# Laser_STM32_System.net
KiCad netlist of a schematic drawn in Altium Designer
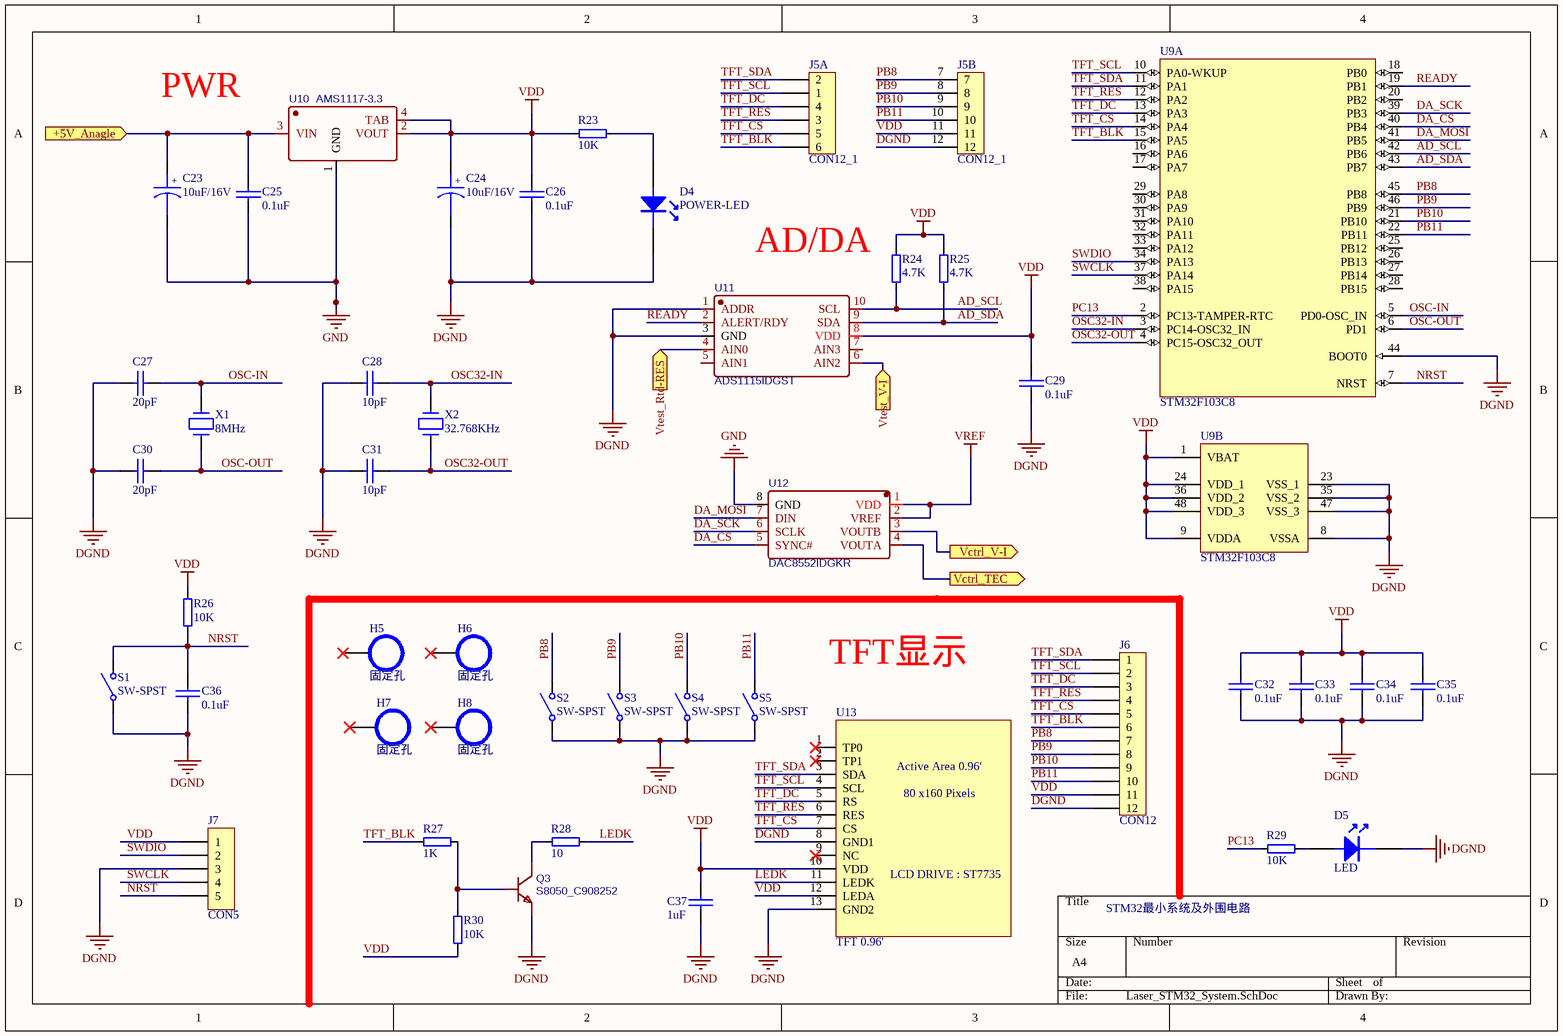
[diagram p0: Laser_STM32_System.SchDoc]

(export (version "E")
  (design (tool "Eeschema 10.0.6"))
  (components
    (comp (ref "C23")
      (value "10uF/16V")
      (footprint "CAP-TH_BD5.0-P2.00-D0.8-FD")
      (description "Capacitor")
      (libsource (lib "Laser Controller") (part "电解电容1"))
    )
    (comp (ref "C24")
      (value "10uF/16V")
      (footprint "CAP-TH_BD5.0-P2.00-D0.8-FD")
      (description "Capacitor")
      (libsource (lib "Laser Controller") (part "电解电容1"))
    )
    (comp (ref "C25")
      (value "0.1uF")
      (footprint "C 0603_M")
      (description "Capacitor")
      (libsource (lib "Laser Controller") (part "普通电容"))
    )
    (comp (ref "C26")
      (value "0.1uF")
      (footprint "C 0603_M")
      (description "Capacitor")
      (libsource (lib "Laser Controller") (part "普通电容"))
    )
    (comp (ref "C27")
      (value "20pF")
      (footprint "C 0603_M")
      (description "Capacitor")
      (libsource (lib "Laser Controller") (part "普通电容"))
    )
    (comp (ref "C28")
      (value "10pF")
      (footprint "C 0603_M")
      (description "Capacitor")
      (libsource (lib "Laser Controller") (part "普通电容"))
    )
    (comp (ref "C29")
      (value "0.1uF")
      (footprint "C 0603_M")
      (description "Capacitor")
      (libsource (lib "Laser Controller") (part "普通电容"))
    )
    (comp (ref "C30")
      (value "20pF")
      (footprint "C 0603_M")
      (description "Capacitor")
      (libsource (lib "Laser Controller") (part "普通电容"))
    )
    (comp (ref "C31")
      (value "10pF")
      (footprint "C 0603_M")
      (description "Capacitor")
      (libsource (lib "Laser Controller") (part "普通电容"))
    )
    (comp (ref "C32")
      (value "0.1uF")
      (footprint "C 0603_M")
      (description "Capacitor")
      (libsource (lib "Laser Controller") (part "普通电容"))
    )
    (comp (ref "C33")
      (value "0.1uF")
      (footprint "C 0603_M")
      (description "Capacitor")
      (libsource (lib "Laser Controller") (part "普通电容"))
    )
    (comp (ref "C34")
      (value "0.1uF")
      (footprint "C 0603_M")
      (description "Capacitor")
      (libsource (lib "Laser Controller") (part "普通电容"))
    )
    (comp (ref "C35")
      (value "0.1uF")
      (footprint "C 0603_M")
      (description "Capacitor")
      (libsource (lib "Laser Controller") (part "普通电容"))
    )
    (comp (ref "C36")
      (value "0.1uF")
      (footprint "C 0603_M")
      (description "Capacitor")
      (libsource (lib "Laser Controller") (part "普通电容"))
    )
    (comp (ref "C37")
      (value "1uF")
      (footprint "C 0603_M")
      (description "Capacitor")
      (libsource (lib "Laser Controller") (part "普通电容"))
    )
    (comp (ref "D4")
      (value "POWER-LED")
      (footprint "LED 0805R")
      (libsource (lib "Laser Controller") (part "发光二极管"))
    )
    (comp (ref "D5")
      (value "LED")
      (footprint "LED 0805R")
      (libsource (lib "Laser Controller") (part "发光二极管"))
    )
    (comp (ref "H5") (value "固定孔") (footprint "铜柱孔3") (libsource (lib "Laser Controller") (part "固定孔")))
    (comp (ref "H6") (value "固定孔") (footprint "铜柱孔3") (libsource (lib "Laser Controller") (part "固定孔")))
    (comp (ref "H7") (value "固定孔") (footprint "铜柱孔3") (libsource (lib "Laser Controller") (part "固定孔")))
    (comp (ref "H8") (value "固定孔") (footprint "铜柱孔3") (libsource (lib "Laser Controller") (part "固定孔")))
    (comp (ref "J5")
      (value "CON12_1")
      (footprint "XH2.54-WI-12P")
      (description "Connector")
      (libsource (lib "") (part "CON12_1_1"))
    )
    (comp (ref "J6")
      (value "CON12")
      (footprint "XH2.54-WI-12P")
      (description "Connector")
      (libsource (lib "Laser Controller") (part "CON12"))
    )
    (comp (ref "J7")
      (value "CON5")
      (footprint "排针-排母:HDR2.54-LI-5P")
      (description "Connector")
      (libsource (lib "Laser Controller") (part "CON5"))
    )
    (comp (ref "Q3")
      (value "S8050_C908252")
      (footprint "SOT-23-3_L2.9-W1.3-P1.90-LS2.4-BR")
      (fields
        (field (name "BOM_SUPPLIER PART") "C908252")
        (field (name "BOM_MANUFACTURER PART") "S8050")
        (field (name "CONTRIBUTOR") "LCSC")
      )
      (libsource (lib "Laser Controller") (part "S8050_C908252"))
    )
    (comp (ref "R23") (value "10K") (footprint "0603R") (libsource (lib "Laser Controller") (part "普通电阻")))
    (comp (ref "R24") (value "4.7K") (footprint "0603R") (libsource (lib "Laser Controller") (part "普通电阻")))
    (comp (ref "R25") (value "4.7K") (footprint "0603R") (libsource (lib "Laser Controller") (part "普通电阻")))
    (comp (ref "R26") (value "10K") (footprint "0603R") (libsource (lib "Laser Controller") (part "普通电阻")))
    (comp (ref "R27") (value "1K") (footprint "0603R") (libsource (lib "Laser Controller") (part "普通电阻")))
    (comp (ref "R28") (value "10") (footprint "0603R") (libsource (lib "Laser Controller") (part "普通电阻")))
    (comp (ref "R29") (value "10K") (footprint "0603R") (libsource (lib "Laser Controller") (part "普通电阻")))
    (comp (ref "R30") (value "10K") (footprint "0603R") (libsource (lib "Laser Controller") (part "普通电阻")))
    (comp (ref "S1")
      (value "SW-SPST")
      (footprint "TSW SMD-3*6*2.5")
      (description "Single-Pole, Single-Throw Switch")
      (fields (field (name "PUBLISHER") "Altium Limited"))
      (libsource (lib "Laser Controller") (part "SW-SPST"))
    )
    (comp (ref "S2")
      (value "SW-SPST")
      (footprint "TSW DIP-6*6*5")
      (description "Single-Pole, Single-Throw Switch")
      (fields (field (name "PUBLISHER") "Altium Limited"))
      (libsource (lib "Laser Controller") (part "SW-SPST"))
    )
    (comp (ref "S3")
      (value "SW-SPST")
      (footprint "TSW DIP-6*6*5")
      (description "Single-Pole, Single-Throw Switch")
      (fields (field (name "PUBLISHER") "Altium Limited"))
      (libsource (lib "Laser Controller") (part "SW-SPST"))
    )
    (comp (ref "S4")
      (value "SW-SPST")
      (footprint "TSW DIP-6*6*5")
      (description "Single-Pole, Single-Throw Switch")
      (fields (field (name "PUBLISHER") "Altium Limited"))
      (libsource (lib "Laser Controller") (part "SW-SPST"))
    )
    (comp (ref "S5")
      (value "SW-SPST")
      (footprint "TSW DIP-6*6*5")
      (description "Single-Pole, Single-Throw Switch")
      (fields (field (name "PUBLISHER") "Altium Limited"))
      (libsource (lib "Laser Controller") (part "SW-SPST"))
    )
    (comp (ref "U9")
      (value "STM32F103C8")
      (footprint "LQFP-48_L7.0-W7.0-P0.50-LS9.0-BL")
      (description "Flaah:64/RAM:20/IO:36")
      (fields (field (name "版权归属") "源创客"))
      (libsource (lib "Laser Controller") (part "STM32F103C8_A"))
    )
    (comp (ref "U10")
      (value "AMS1117-3.3")
      (footprint "SOT-223-4_L6.5-W3.5-P2.30-LS7.0-BR")
      (fields (field (name "BOM_SUPPLIER PART") "C347256") (field (name "CONTRIBUTOR") "LCSC"))
      (libsource (lib "Laser Controller") (part "AMS1117-3.3"))
    )
    (comp (ref "U11")
      (value "ADS1115IDGST")
      (footprint "VSSOP-10_L3.0-W3.0-P0.50-LS4.9-BL")
      (fields (field (name "BOM_SUPPLIER PART") "C468683") (field (name "CONTRIBUTOR") "LCSC"))
      (libsource (lib "Laser Controller") (part "ADS1115IDGST"))
    )
    (comp (ref "U12")
      (value "DAC8552IDGKR")
      (footprint "VSSOP-8_L3.0-W3.0-P0.65-LS5.0-BL")
      (fields (field (name "BOM_SUPPLIER PART") "C136020") (field (name "CONTRIBUTOR") "LCSC"))
      (libsource (lib "Laser Controller") (part "DAC8552IDGKR"))
    )
    (comp (ref "U13")
      (value "TFT 0.96'")
      (footprint "TFT0.96-13P")
      (libsource (lib "Laser Controller") (part "TFT显示屏"))
    )
    (comp (ref "X1")
      (value "8MHz")
      (footprint "OSC HC-49S")
      (description "Crystal")
      (libsource (lib "Laser Controller") (part "CRYSTAL"))
    )
    (comp (ref "X2")
      (value "32.768KHz")
      (footprint "OSC-3x8-LI")
      (description "Crystal")
      (libsource (lib "Laser Controller") (part "CRYSTAL"))
    )
  )
  (nets
    (net (code "1") (name "/+5V_Anagle") (class "Default")
      (node (ref "C23") (pin "1") (pinfunction "1_1") (pintype "passive"))
      (node (ref "C25") (pin "1") (pinfunction "1_1") (pintype "passive"))
      (node (ref "U10") (pin "3") (pinfunction "VIN_3") (pintype "passive"))
    )
    (net (code "2") (name "/AD_SCL") (class "Default")
      (node (ref "R24") (pin "1") (pinfunction "1_1") (pintype "passive"))
      (node (ref "U11") (pin "10") (pinfunction "SCL_10") (pintype "passive"))
      (node (ref "U9") (pin "42") (pinfunction "PB6_42") (pintype "bidirectional"))
    )
    (net (code "3") (name "/AD_SDA") (class "Default")
      (node (ref "R25") (pin "1") (pinfunction "1_1") (pintype "passive"))
      (node (ref "U11") (pin "9") (pinfunction "SDA_9") (pintype "passive"))
      (node (ref "U9") (pin "43") (pinfunction "PB7_43") (pintype "bidirectional"))
    )
    (net (code "4") (name "/DA_MOSI") (class "Default")
      (node (ref "U12") (pin "7") (pinfunction "DIN_7") (pintype "passive"))
      (node (ref "U9") (pin "41") (pinfunction "PB5_41") (pintype "bidirectional"))
    )
    (net (code "5") (name "/DA_SCK") (class "Default")
      (node (ref "U12") (pin "6") (pinfunction "SCLK_6") (pintype "passive"))
      (node (ref "U9") (pin "39") (pinfunction "PB3_39") (pintype "bidirectional"))
    )
    (net (code "6") (name "/DA_~{CS}") (class "Default")
      (node (ref "U12") (pin "5") (pinfunction "SYNC#_5") (pintype "passive"))
      (node (ref "U9") (pin "40") (pinfunction "PB4_40") (pintype "bidirectional"))
    )
    (net (code "7") (name "/LEDK") (class "Default")
      (node (ref "R28") (pin "2") (pinfunction "2_2") (pintype "passive"))
      (node (ref "U13") (pin "11") (pinfunction "LEDK_11") (pintype "passive"))
    )
    (net (code "8") (name "/NRST") (class "Default")
      (node (ref "C36") (pin "1") (pinfunction "1_1") (pintype "passive"))
      (node (ref "J7") (pin "5") (pinfunction "5_5") (pintype "passive"))
      (node (ref "R26") (pin "1") (pinfunction "1_1") (pintype "passive"))
      (node (ref "S1") (pin "2") (pinfunction "NO_2") (pintype "passive"))
      (node (ref "U9") (pin "7") (pinfunction "NRST_7") (pintype "bidirectional"))
    )
    (net (code "9") (name "/OSC-IN") (class "Default")
      (node (ref "C27") (pin "2") (pinfunction "2_2") (pintype "passive"))
      (node (ref "U9") (pin "5") (pinfunction "PD0-OSC_IN_5") (pintype "bidirectional"))
      (node (ref "X1") (pin "2") (pinfunction "2_2") (pintype "passive"))
    )
    (net (code "10") (name "/OSC-OUT") (class "Default")
      (node (ref "C30") (pin "2") (pinfunction "2_2") (pintype "passive"))
      (node (ref "U9") (pin "6") (pinfunction "PD1_6") (pintype "bidirectional"))
      (node (ref "X1") (pin "1") (pinfunction "1_1") (pintype "passive"))
    )
    (net (code "11") (name "/OSC32-IN") (class "Default")
      (node (ref "C28") (pin "2") (pinfunction "2_2") (pintype "passive"))
      (node (ref "U9") (pin "3") (pinfunction "PC14-OSC32_IN_3") (pintype "bidirectional"))
      (node (ref "X2") (pin "2") (pinfunction "2_2") (pintype "passive"))
    )
    (net (code "12") (name "/OSC32-OUT") (class "Default")
      (node (ref "C31") (pin "2") (pinfunction "2_2") (pintype "passive"))
      (node (ref "U9") (pin "4") (pinfunction "PC15-OSC32_OUT_4") (pintype "bidirectional"))
      (node (ref "X2") (pin "1") (pinfunction "1_1") (pintype "passive"))
    )
    (net (code "13") (name "/PB8") (class "Default")
      (node (ref "J5") (pin "7") (pinfunction "7_7") (pintype "passive"))
      (node (ref "J6") (pin "7") (pinfunction "7_7") (pintype "passive"))
      (node (ref "S2") (pin "2") (pinfunction "NO_2") (pintype "passive"))
      (node (ref "U9") (pin "45") (pinfunction "PB8_45") (pintype "bidirectional"))
    )
    (net (code "14") (name "/PB9") (class "Default")
      (node (ref "J5") (pin "8") (pinfunction "8_8") (pintype "passive"))
      (node (ref "J6") (pin "8") (pinfunction "8_8") (pintype "passive"))
      (node (ref "S3") (pin "2") (pinfunction "NO_2") (pintype "passive"))
      (node (ref "U9") (pin "46") (pinfunction "PB9_46") (pintype "bidirectional"))
    )
    (net (code "15") (name "/PB10") (class "Default")
      (node (ref "J5") (pin "9") (pinfunction "9_9") (pintype "passive"))
      (node (ref "J6") (pin "9") (pinfunction "9_9") (pintype "passive"))
      (node (ref "S4") (pin "2") (pinfunction "NO_2") (pintype "passive"))
      (node (ref "U9") (pin "21") (pinfunction "PB10_21") (pintype "bidirectional"))
    )
    (net (code "16") (name "/PB11") (class "Default")
      (node (ref "J5") (pin "10") (pinfunction "10_10") (pintype "passive"))
      (node (ref "J6") (pin "10") (pinfunction "10_10") (pintype "passive"))
      (node (ref "S5") (pin "2") (pinfunction "NO_2") (pintype "passive"))
      (node (ref "U9") (pin "22") (pinfunction "PB11_22") (pintype "bidirectional"))
    )
    (net (code "17") (name "/PC13") (class "Default")
      (node (ref "R29") (pin "1") (pinfunction "1_1") (pintype "passive"))
      (node (ref "U9") (pin "2") (pinfunction "PC13-TAMPER-RTC_2") (pintype "bidirectional"))
    )
    (net (code "18") (name "/READY") (class "Default")
      (node (ref "U11") (pin "2") (pinfunction "ALERT/RDY_2") (pintype "passive"))
      (node (ref "U9") (pin "19") (pinfunction "PB1_19") (pintype "bidirectional"))
    )
    (net (code "19") (name "/SWCLK") (class "Default")
      (node (ref "J7") (pin "4") (pinfunction "4_4") (pintype "passive"))
      (node (ref "U9") (pin "37") (pinfunction "PA14_37") (pintype "bidirectional"))
    )
    (net (code "20") (name "/SWDIO") (class "Default")
      (node (ref "J7") (pin "2") (pinfunction "2_2") (pintype "passive"))
      (node (ref "U9") (pin "34") (pinfunction "PA13_34") (pintype "bidirectional"))
    )
    (net (code "21") (name "/TFT_BLK") (class "Default")
      (node (ref "J5") (pin "6") (pinfunction "6_6") (pintype "passive"))
      (node (ref "J6") (pin "6") (pinfunction "6_6") (pintype "passive"))
      (node (ref "R27") (pin "1") (pinfunction "1_1") (pintype "passive"))
      (node (ref "U9") (pin "15") (pinfunction "PA5_15") (pintype "bidirectional"))
    )
    (net (code "22") (name "/TFT_CS") (class "Default")
      (node (ref "J5") (pin "5") (pinfunction "5_5") (pintype "passive"))
      (node (ref "J6") (pin "5") (pinfunction "5_5") (pintype "passive"))
      (node (ref "U13") (pin "7") (pinfunction "CS_7") (pintype "passive"))
      (node (ref "U9") (pin "14") (pinfunction "PA4_14") (pintype "bidirectional"))
    )
    (net (code "23") (name "/TFT_DC") (class "Default")
      (node (ref "J5") (pin "4") (pinfunction "4_4") (pintype "passive"))
      (node (ref "J6") (pin "3") (pinfunction "3_3") (pintype "passive"))
      (node (ref "U13") (pin "5") (pinfunction "RS_5") (pintype "passive"))
      (node (ref "U9") (pin "13") (pinfunction "PA3_13") (pintype "bidirectional"))
    )
    (net (code "24") (name "/TFT_RES") (class "Default")
      (node (ref "J5") (pin "3") (pinfunction "3_3") (pintype "passive"))
      (node (ref "J6") (pin "4") (pinfunction "4_4") (pintype "passive"))
      (node (ref "U13") (pin "6") (pinfunction "RES_6") (pintype "passive"))
      (node (ref "U9") (pin "12") (pinfunction "PA2_12") (pintype "bidirectional"))
    )
    (net (code "25") (name "/TFT_SCL") (class "Default")
      (node (ref "J5") (pin "1") (pinfunction "1_1") (pintype "passive"))
      (node (ref "J6") (pin "2") (pinfunction "2_2") (pintype "passive"))
      (node (ref "U13") (pin "4") (pinfunction "SCL_4") (pintype "passive"))
      (node (ref "U9") (pin "10") (pinfunction "PA0-WKUP_10") (pintype "bidirectional"))
    )
    (net (code "26") (name "/TFT_SDA") (class "Default")
      (node (ref "J5") (pin "2") (pinfunction "2_2") (pintype "passive"))
      (node (ref "J6") (pin "1") (pinfunction "1_1") (pintype "passive"))
      (node (ref "U13") (pin "3") (pinfunction "SDA_3") (pintype "passive"))
      (node (ref "U9") (pin "11") (pinfunction "PA1_11") (pintype "bidirectional"))
    )
    (net (code "27") (name "/Vctrl_TEC") (class "Default")
      (node (ref "U12") (pin "4") (pinfunction "VOUTA_4") (pintype "passive"))
    )
    (net (code "28") (name "/Vctrl_V-I") (class "Default")
      (node (ref "U12") (pin "3") (pinfunction "VOUTB_3") (pintype "passive"))
    )
    (net (code "29") (name "/Vtest_Rtd-RES") (class "Default")
      (node (ref "U11") (pin "4") (pinfunction "AIN0_4") (pintype "passive"))
    )
    (net (code "30") (name "/Vtest_V-I") (class "Default")
      (node (ref "U11") (pin "6") (pinfunction "AIN2_6") (pintype "passive"))
    )
    (net (code "31") (name "DGND") (class "Default")
      (node (ref "C24") (pin "2") (pinfunction "2_2") (pintype "passive"))
      (node (ref "C26") (pin "2") (pinfunction "2_2") (pintype "passive"))
      (node (ref "C27") (pin "1") (pinfunction "1_1") (pintype "passive"))
      (node (ref "C28") (pin "1") (pinfunction "1_1") (pintype "passive"))
      (node (ref "C29") (pin "2") (pinfunction "2_2") (pintype "passive"))
      (node (ref "C30") (pin "1") (pinfunction "1_1") (pintype "passive"))
      (node (ref "C31") (pin "1") (pinfunction "1_1") (pintype "passive"))
      (node (ref "C32") (pin "2") (pinfunction "2_2") (pintype "passive"))
      (node (ref "C33") (pin "2") (pinfunction "2_2") (pintype "passive"))
      (node (ref "C34") (pin "2") (pinfunction "2_2") (pintype "passive"))
      (node (ref "C35") (pin "2") (pinfunction "2_2") (pintype "passive"))
      (node (ref "C36") (pin "2") (pinfunction "2_2") (pintype "passive"))
      (node (ref "C37") (pin "1") (pinfunction "1_1") (pintype "passive"))
      (node (ref "D4") (pin "2") (pinfunction "2_2") (pintype "passive"))
      (node (ref "D5") (pin "2") (pinfunction "2_2") (pintype "passive"))
      (node (ref "J5") (pin "12") (pinfunction "12_12") (pintype "passive"))
      (node (ref "J6") (pin "12") (pinfunction "12_12") (pintype "passive"))
      (node (ref "J7") (pin "3") (pinfunction "3_3") (pintype "passive"))
      (node (ref "Q3") (pin "2") (pinfunction "E_2") (pintype "passive"))
      (node (ref "S1") (pin "1") (pinfunction "COMMON_1") (pintype "passive"))
      (node (ref "S2") (pin "1") (pinfunction "COMMON_1") (pintype "passive"))
      (node (ref "S3") (pin "1") (pinfunction "COMMON_1") (pintype "passive"))
      (node (ref "S4") (pin "1") (pinfunction "COMMON_1") (pintype "passive"))
      (node (ref "S5") (pin "1") (pinfunction "COMMON_1") (pintype "passive"))
      (node (ref "U11") (pin "1") (pinfunction "ADDR_1") (pintype "passive"))
      (node (ref "U11") (pin "3") (pinfunction "GND_3") (pintype "passive"))
      (node (ref "U13") (pin "13") (pinfunction "GND2_13") (pintype "passive"))
      (node (ref "U13") (pin "8") (pinfunction "GND1_8") (pintype "passive"))
      (node (ref "U9") (pin "23") (pinfunction "VSS_1_23") (pintype "power_in"))
      (node (ref "U9") (pin "35") (pinfunction "VSS_2_35") (pintype "power_in"))
      (node (ref "U9") (pin "44") (pinfunction "BOOT0_44") (pintype "input"))
      (node (ref "U9") (pin "47") (pinfunction "VSS_3_47") (pintype "power_in"))
      (node (ref "U9") (pin "8") (pinfunction "VSSA_8") (pintype "power_in"))
    )
    (net (code "32") (name "GND") (class "Default")
      (node (ref "C23") (pin "2") (pinfunction "2_2") (pintype "passive"))
      (node (ref "C25") (pin "2") (pinfunction "2_2") (pintype "passive"))
      (node (ref "U10") (pin "1") (pinfunction "GND_1") (pintype "passive"))
      (node (ref "U12") (pin "8") (pinfunction "GND_8") (pintype "passive"))
    )
    (net (code "33") (name "Net-(D4-Pad1)") (class "Default")
      (node (ref "D4") (pin "1") (pinfunction "1_1") (pintype "passive"))
      (node (ref "R23") (pin "2") (pinfunction "2_2") (pintype "passive"))
    )
    (net (code "34") (name "Net-(D5-Pad1)") (class "Default")
      (node (ref "D5") (pin "1") (pinfunction "1_1") (pintype "passive"))
      (node (ref "R29") (pin "2") (pinfunction "2_2") (pintype "passive"))
    )
    (net (code "35") (name "Net-(Q3-B)") (class "Default")
      (node (ref "Q3") (pin "1") (pinfunction "B_1") (pintype "passive"))
      (node (ref "R27") (pin "2") (pinfunction "2_2") (pintype "passive"))
      (node (ref "R30") (pin "2") (pinfunction "2_2") (pintype "passive"))
    )
    (net (code "36") (name "Net-(Q3-C)") (class "Default")
      (node (ref "Q3") (pin "3") (pinfunction "C_3") (pintype "passive"))
      (node (ref "R28") (pin "1") (pinfunction "1_1") (pintype "passive"))
    )
    (net (code "37") (name "VDD") (class "Default")
      (node (ref "C24") (pin "1") (pinfunction "1_1") (pintype "passive"))
      (node (ref "C26") (pin "1") (pinfunction "1_1") (pintype "passive"))
      (node (ref "C29") (pin "1") (pinfunction "1_1") (pintype "passive"))
      (node (ref "C32") (pin "1") (pinfunction "1_1") (pintype "passive"))
      (node (ref "C33") (pin "1") (pinfunction "1_1") (pintype "passive"))
      (node (ref "C34") (pin "1") (pinfunction "1_1") (pintype "passive"))
      (node (ref "C35") (pin "1") (pinfunction "1_1") (pintype "passive"))
      (node (ref "C37") (pin "2") (pinfunction "2_2") (pintype "passive"))
      (node (ref "J5") (pin "11") (pinfunction "11_11") (pintype "passive"))
      (node (ref "J6") (pin "11") (pinfunction "11_11") (pintype "passive"))
      (node (ref "J7") (pin "1") (pinfunction "1_1") (pintype "passive"))
      (node (ref "R23") (pin "1") (pinfunction "1_1") (pintype "passive"))
      (node (ref "R24") (pin "2") (pinfunction "2_2") (pintype "passive"))
      (node (ref "R25") (pin "2") (pinfunction "2_2") (pintype "passive"))
      (node (ref "R26") (pin "2") (pinfunction "2_2") (pintype "passive"))
      (node (ref "R30") (pin "1") (pinfunction "1_1") (pintype "passive"))
      (node (ref "U10") (pin "2") (pinfunction "VOUT_2") (pintype "passive"))
      (node (ref "U10") (pin "4") (pinfunction "TAB_4") (pintype "passive"))
      (node (ref "U11") (pin "8") (pinfunction "VDD_8") (pintype "passive"))
      (node (ref "U13") (pin "10") (pinfunction "VDD_10") (pintype "passive"))
      (node (ref "U13") (pin "12") (pinfunction "LEDA_12") (pintype "passive"))
      (node (ref "U9") (pin "1") (pinfunction "VBAT_1") (pintype "power_in"))
      (node (ref "U9") (pin "24") (pinfunction "VDD_1_24") (pintype "power_in"))
      (node (ref "U9") (pin "36") (pinfunction "VDD_2_36") (pintype "power_in"))
      (node (ref "U9") (pin "48") (pinfunction "VDD_3_48") (pintype "power_in"))
      (node (ref "U9") (pin "9") (pinfunction "VDDA_9") (pintype "power_in"))
    )
    (net (code "38") (name "VREF") (class "Default")
      (node (ref "U12") (pin "1") (pinfunction "VDD_1") (pintype "passive"))
      (node (ref "U12") (pin "2") (pinfunction "VREF_2") (pintype "passive"))
    )
    (net (code "39") (name "unconnected-(H5-Pad11)") (class "Default")
      (node (ref "H5") (pin "11") (pinfunction "11_11") (pintype "passive+no_connect"))
    )
    (net (code "40") (name "unconnected-(H6-Pad11)") (class "Default")
      (node (ref "H6") (pin "11") (pinfunction "11_11") (pintype "passive+no_connect"))
    )
    (net (code "41") (name "unconnected-(H7-Pad11)") (class "Default")
      (node (ref "H7") (pin "11") (pinfunction "11_11") (pintype "passive+no_connect"))
    )
    (net (code "42") (name "unconnected-(H8-Pad11)") (class "Default")
      (node (ref "H8") (pin "11") (pinfunction "11_11") (pintype "passive+no_connect"))
    )
    (net (code "43") (name "unconnected-(U9A-PA6-Pad16)") (class "Default")
      (node (ref "U9") (pin "16") (pinfunction "PA6_16") (pintype "bidirectional"))
    )
    (net (code "44") (name "unconnected-(U9A-PA7-Pad17)") (class "Default")
      (node (ref "U9") (pin "17") (pinfunction "PA7_17") (pintype "bidirectional"))
    )
    (net (code "45") (name "unconnected-(U9A-PA8-Pad29)") (class "Default")
      (node (ref "U9") (pin "29") (pinfunction "PA8_29") (pintype "bidirectional"))
    )
    (net (code "46") (name "unconnected-(U9A-PA9-Pad30)") (class "Default")
      (node (ref "U9") (pin "30") (pinfunction "PA9_30") (pintype "bidirectional"))
    )
    (net (code "47") (name "unconnected-(U9A-PA10-Pad31)") (class "Default")
      (node (ref "U9") (pin "31") (pinfunction "PA10_31") (pintype "bidirectional"))
    )
    (net (code "48") (name "unconnected-(U9A-PA11-Pad32)") (class "Default")
      (node (ref "U9") (pin "32") (pinfunction "PA11_32") (pintype "bidirectional"))
    )
    (net (code "49") (name "unconnected-(U9A-PA12-Pad33)") (class "Default")
      (node (ref "U9") (pin "33") (pinfunction "PA12_33") (pintype "bidirectional"))
    )
    (net (code "50") (name "unconnected-(U9A-PA15-Pad38)") (class "Default")
      (node (ref "U9") (pin "38") (pinfunction "PA15_38") (pintype "bidirectional"))
    )
    (net (code "51") (name "unconnected-(U9A-PB0-Pad18)") (class "Default")
      (node (ref "U9") (pin "18") (pinfunction "PB0_18") (pintype "bidirectional"))
    )
    (net (code "52") (name "unconnected-(U9A-PB2-Pad20)") (class "Default")
      (node (ref "U9") (pin "20") (pinfunction "PB2_20") (pintype "bidirectional"))
    )
    (net (code "53") (name "unconnected-(U9A-PB12-Pad25)") (class "Default")
      (node (ref "U9") (pin "25") (pinfunction "PB12_25") (pintype "bidirectional"))
    )
    (net (code "54") (name "unconnected-(U9A-PB13-Pad26)") (class "Default")
      (node (ref "U9") (pin "26") (pinfunction "PB13_26") (pintype "bidirectional"))
    )
    (net (code "55") (name "unconnected-(U9A-PB14-Pad27)") (class "Default")
      (node (ref "U9") (pin "27") (pinfunction "PB14_27") (pintype "bidirectional"))
    )
    (net (code "56") (name "unconnected-(U9A-PB15-Pad28)") (class "Default")
      (node (ref "U9") (pin "28") (pinfunction "PB15_28") (pintype "bidirectional"))
    )
    (net (code "57") (name "unconnected-(U11-AIN1-Pad5)") (class "Default")
      (node (ref "U11") (pin "5") (pinfunction "AIN1_5") (pintype "passive"))
    )
    (net (code "58") (name "unconnected-(U11-AIN3-Pad7)") (class "Default")
      (node (ref "U11") (pin "7") (pinfunction "AIN3_7") (pintype "passive"))
    )
    (net (code "59") (name "unconnected-(U13-NC-Pad9)") (class "Default")
      (node (ref "U13") (pin "9") (pinfunction "NC_9") (pintype "passive+no_connect"))
    )
    (net (code "60") (name "unconnected-(U13-TP0-Pad1)") (class "Default")
      (node (ref "U13") (pin "1") (pinfunction "TP0_1") (pintype "passive+no_connect"))
    )
    (net (code "61") (name "unconnected-(U13-TP1-Pad2)") (class "Default")
      (node (ref "U13") (pin "2") (pinfunction "TP1_2") (pintype "passive+no_connect"))
    )
  )
)
